# 1_AASTM32-Power.net
KiCad netlist of a schematic drawn in Altium Designer
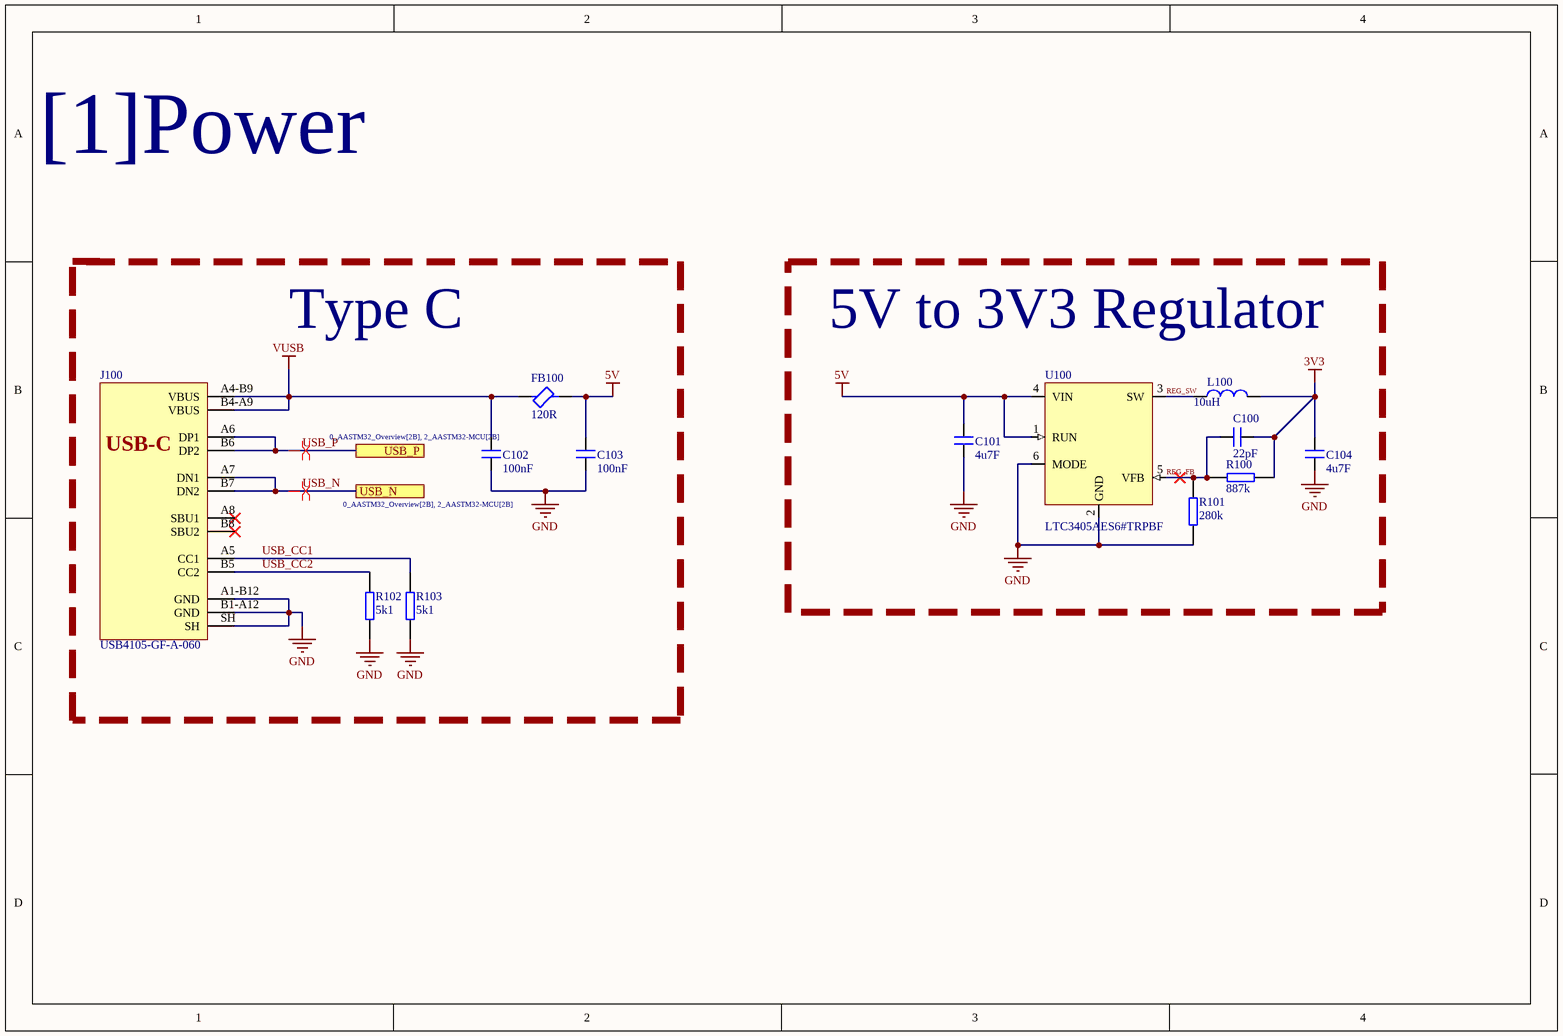
[diagram p0: 1_AASTM32-Power.SchDoc]

(export (version "E")
  (design (tool "Eeschema 10.0.6"))
  (components
    (comp (ref "C100")
      (value "22pF")
      (footprint "0603 CAP")
      (fields
        (field (name "MANUFACTURER") "Samsung")
        (field (name "MANUFACTURER PART NUMBER") "CL10A475KA8NQNC")
      )
      (libsource (lib "GenerALI") (part "0603 4u7 CAP"))
    )
    (comp (ref "C101")
      (value "4u7F")
      (footprint "0603 CAP")
      (fields
        (field (name "MANUFACTURER") "Samsung")
        (field (name "MANUFACTURER PART NUMBER") "CL10A475KA8NQNC")
      )
      (libsource (lib "GenerALI") (part "0603 4u7 CAP"))
    )
    (comp (ref "C102")
      (value "100nF")
      (footprint "0603 CAP")
      (fields
        (field (name "MANUFACTURER") "Samsung")
        (field (name "MANUFACTURER PART NUMBER") "CL10A475KA8NQNC")
      )
      (libsource (lib "GenerALI") (part "0603 4u7 CAP"))
    )
    (comp (ref "C103")
      (value "100nF")
      (footprint "0603 CAP")
      (fields
        (field (name "MANUFACTURER") "Samsung")
        (field (name "MANUFACTURER PART NUMBER") "CL10A475KA8NQNC")
      )
      (libsource (lib "GenerALI") (part "0603 4u7 CAP"))
    )
    (comp (ref "C104")
      (value "4u7F")
      (footprint "0603 CAP")
      (fields
        (field (name "MANUFACTURER") "Samsung")
        (field (name "MANUFACTURER PART NUMBER") "CL10A475KA8NQNC")
      )
      (libsource (lib "GenerALI") (part "0603 4u7 CAP"))
    )
    (comp (ref "FB100")
      (value "120R")
      (footprint "0402 RES")
      (description "Ferrite Chip, 1 Function(s), 0.9A, 2 Pin(s)\r\nBLM15PD121SN1D")
      (fields
        (field (name "MANUFACTURER") "Murata")
        (field (name "MANUFACTURER PART NUMBER") "BLM15PD121SN1D")
      )
      (libsource (lib "GenerALI") (part "Ferritte Bead 120R 0402"))
    )
    (comp (ref "J100")
      (value "USB4105-GF-A-060")
      (footprint "USB TYPE C GCT 16P")
      (description "USB Connectors USB Type C, 2.0 SMT PCB Top Mnt .60mm")
      (fields (field (name "MANUFACTURER") "GCT"))
      (libsource (lib "GenerALI") (part "USB TYPE C 16 PIN GCT"))
    )
    (comp (ref "L100")
      (value "10uH")
      (footprint "NRH2412")
      (description "Power Inductors - SMD 963-LSXNE2424MKT100M RPLCMT PN 2412 10uH 600mOhms")
      (fields
        (field (name "MANUFACTURER") "TAIYO YUDEN")
        (field (name "MANUFACTURER PART NUMBER") "NRH2412T100MNGH")
      )
      (libsource (lib "GenerALI") (part "NRH2412T100MNGH"))
    )
    (comp (ref "R100")
      (value "887k")
      (footprint "0603 RES")
      (libsource (lib "GenerALI") (part "0603 680R RES"))
    )
    (comp (ref "R101")
      (value "280k")
      (footprint "0603 RES")
      (libsource (lib "GenerALI") (part "0603 680R RES"))
    )
    (comp (ref "R102")
      (value "5k1")
      (footprint "0603 RES")
      (libsource (lib "GenerALI") (part "0603 10k RES"))
    )
    (comp (ref "R103")
      (value "5k1")
      (footprint "0603 RES")
      (libsource (lib "GenerALI") (part "0603 10k RES"))
    )
    (comp (ref "U100")
      (value "LTC3405AES6#TRPBF")
      (footprint "SOT23-6")
      (description "1.5MHz, 300mA Synchronous Step-Down Regulator in ThinSOT")
      (fields (field (name "MANUFACTURER") "Analog Devices"))
      (libsource (lib "GenerALI") (part "LTC3405AES6#TRPBF"))
    )
  )
  (nets
    (net (code "1") (name "/REG_FB") (class "Default")
      (node (ref "C100") (pin "2") (pinfunction "2_2") (pintype "passive"))
      (node (ref "R100") (pin "2") (pinfunction "2_2") (pintype "passive"))
      (node (ref "R101") (pin "2") (pinfunction "2_2") (pintype "passive"))
      (node (ref "U100") (pin "5") (pinfunction "VFB_5") (pintype "input"))
    )
    (net (code "2") (name "/REG_SW") (class "Default")
      (node (ref "L100") (pin "1") (pinfunction "1_1") (pintype "passive"))
      (node (ref "U100") (pin "3") (pinfunction "SW_3") (pintype "power_in"))
    )
    (net (code "3") (name "/USB_CC1") (class "Default")
      (node (ref "J100") (pin "A5") (pinfunction "CC1_A5") (pintype "passive"))
      (node (ref "R103") (pin "2") (pinfunction "2_2") (pintype "passive"))
    )
    (net (code "4") (name "/USB_CC2") (class "Default")
      (node (ref "J100") (pin "B5") (pinfunction "CC2_B5") (pintype "passive"))
      (node (ref "R102") (pin "2") (pinfunction "2_2") (pintype "passive"))
    )
    (net (code "5") (name "/USB_N") (class "Default")
      (node (ref "J100") (pin "A7") (pinfunction "DN1_A7") (pintype "passive"))
      (node (ref "J100") (pin "B7") (pinfunction "DN2_B7") (pintype "passive"))
    )
    (net (code "6") (name "/USB_P") (class "Default")
      (node (ref "J100") (pin "A6") (pinfunction "DP1_A6") (pintype "passive"))
      (node (ref "J100") (pin "B6") (pinfunction "DP2_B6") (pintype "passive"))
    )
    (net (code "7") (name "3V3") (class "Default")
      (node (ref "C100") (pin "1") (pinfunction "1_1") (pintype "passive"))
      (node (ref "C104") (pin "2") (pinfunction "2_2") (pintype "passive"))
      (node (ref "L100") (pin "2") (pinfunction "2_2") (pintype "passive"))
      (node (ref "R100") (pin "1") (pinfunction "1_1") (pintype "passive"))
    )
    (net (code "8") (name "5V") (class "Default")
      (node (ref "C101") (pin "2") (pinfunction "2_2") (pintype "passive"))
      (node (ref "C103") (pin "2") (pinfunction "2_2") (pintype "passive"))
      (node (ref "FB100") (pin "2") (pinfunction "2_2") (pintype "passive"))
      (node (ref "U100") (pin "1") (pinfunction "RUN_1") (pintype "input"))
      (node (ref "U100") (pin "4") (pinfunction "VIN_4") (pintype "power_in"))
    )
    (net (code "9") (name "GND") (class "Default")
      (node (ref "C101") (pin "1") (pinfunction "1_1") (pintype "passive"))
      (node (ref "C102") (pin "1") (pinfunction "1_1") (pintype "passive"))
      (node (ref "C103") (pin "1") (pinfunction "1_1") (pintype "passive"))
      (node (ref "C104") (pin "1") (pinfunction "1_1") (pintype "passive"))
      (node (ref "J100") (pin "A1-B12") (pinfunction "GND_A1-B12") (pintype "passive"))
      (node (ref "J100") (pin "B1-A12") (pinfunction "GND_B1-A12") (pintype "passive"))
      (node (ref "J100") (pin "SH") (pinfunction "SH_SH") (pintype "passive"))
      (node (ref "R101") (pin "1") (pinfunction "1_1") (pintype "passive"))
      (node (ref "R102") (pin "1") (pinfunction "1_1") (pintype "passive"))
      (node (ref "R103") (pin "1") (pinfunction "1_1") (pintype "passive"))
      (node (ref "U100") (pin "2") (pinfunction "GND_2") (pintype "power_in"))
      (node (ref "U100") (pin "6") (pinfunction "MODE_6") (pintype "passive"))
    )
    (net (code "10") (name "VUSB") (class "Default")
      (node (ref "C102") (pin "2") (pinfunction "2_2") (pintype "passive"))
      (node (ref "FB100") (pin "1") (pinfunction "1_1") (pintype "passive"))
      (node (ref "J100") (pin "A4-B9") (pinfunction "VBUS_A4-B9") (pintype "passive"))
      (node (ref "J100") (pin "B4-A9") (pinfunction "VBUS_B4-A9") (pintype "passive"))
    )
    (net (code "11") (name "unconnected-(J100-SBU1-PadA8)") (class "Default")
      (node (ref "J100") (pin "A8") (pinfunction "SBU1_A8") (pintype "passive+no_connect"))
    )
    (net (code "12") (name "unconnected-(J100-SBU2-PadB8)") (class "Default")
      (node (ref "J100") (pin "B8") (pinfunction "SBU2_B8") (pintype "passive+no_connect"))
    )
  )
)
